# Aero_Board_2022.net
KiCad netlist of a schematic drawn in EAGLE
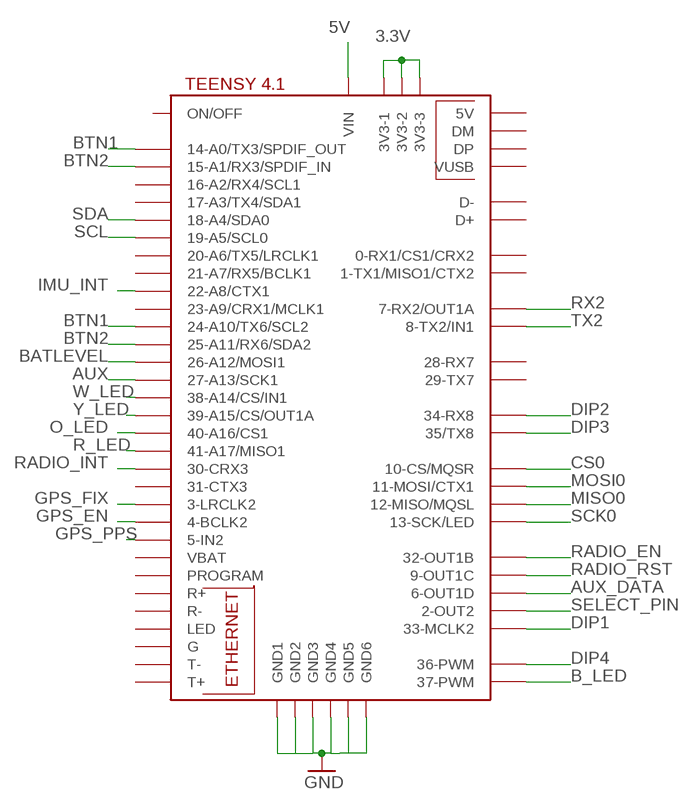
[diagram p0: schematic, sheet 1]
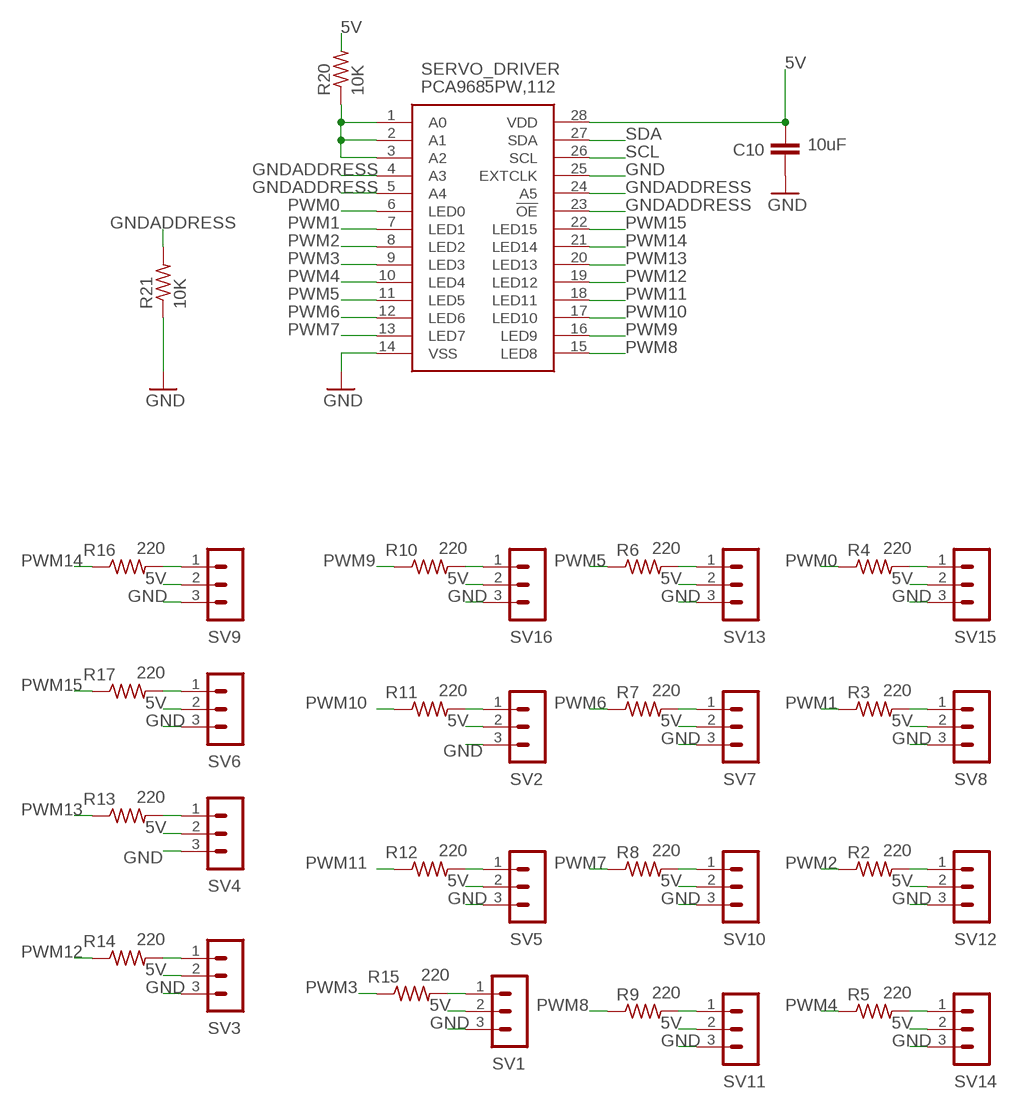
[diagram p1: schematic, sheet 2]
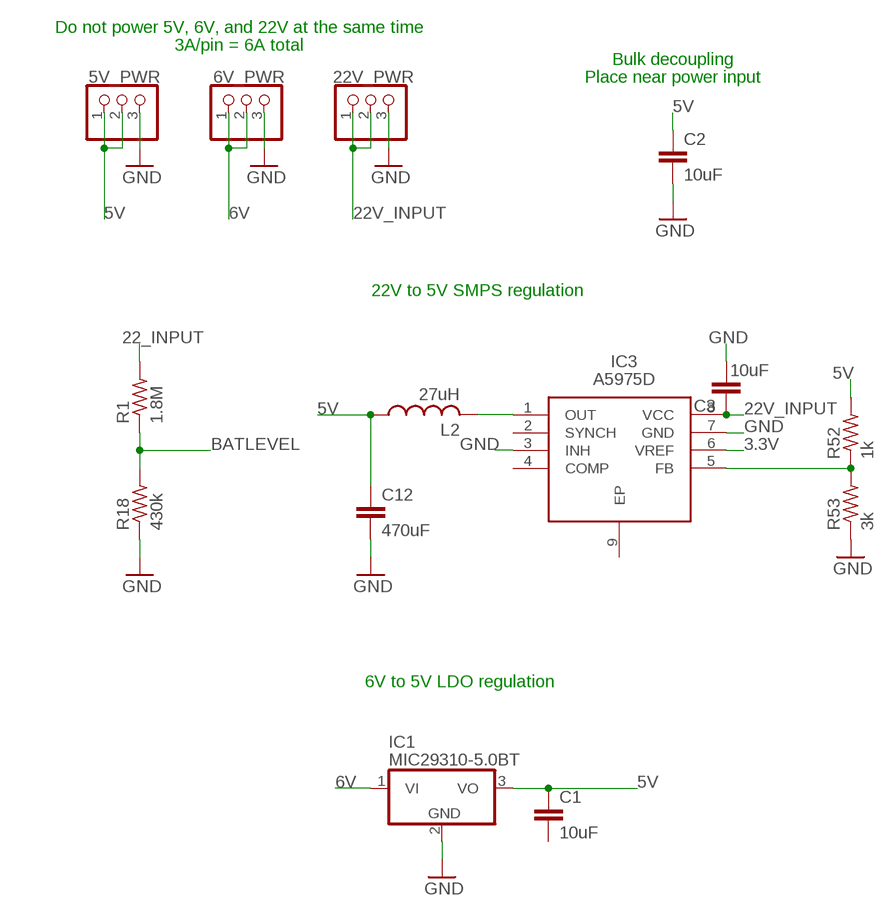
[diagram p2: schematic, sheet 3]
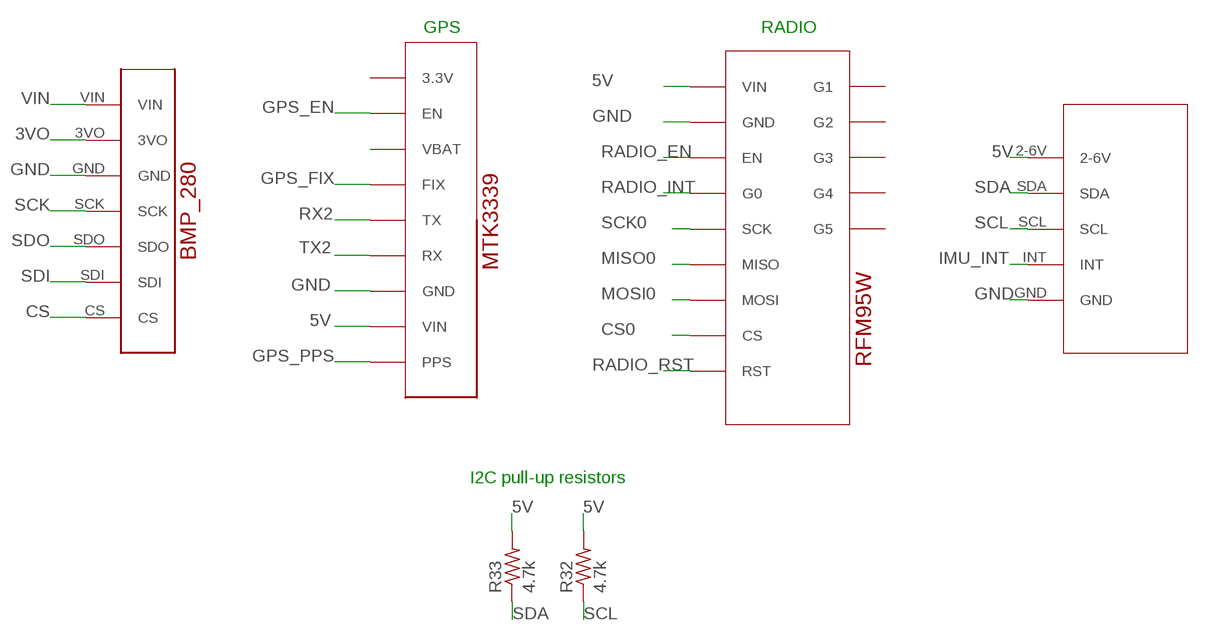
[diagram p3: schematic, sheet 4]
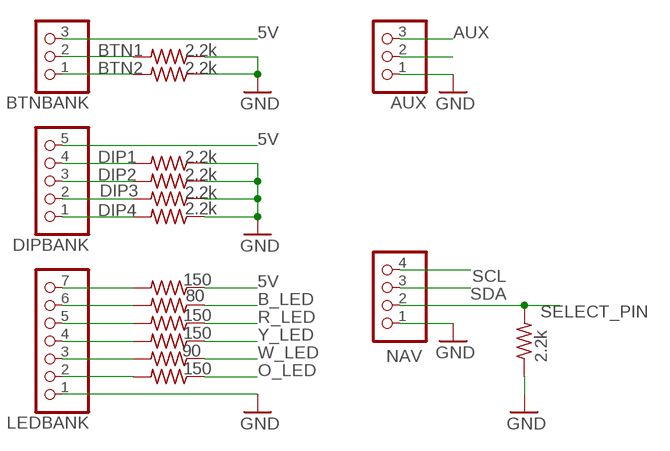
[diagram p4: schematic, sheet 5]
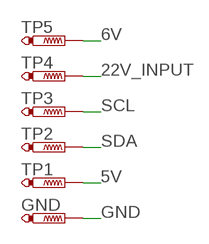
[diagram p5: schematic, sheet 6]

(export (version "E")
  (design (tool "Eeschema 10.0.6"))
  (components
    (comp (ref "TEENSY4.1")
      (value "TEENSY41")
      (footprint "eagle-import:TEENSY41")
      (libsource (lib "eagle-import") (part "TEENSY41"))
    )
    (comp (ref "GND")
      (value "PTR1B1,27")
      (footprint "eagle-import:B1,27")
      (libsource (lib "eagle-import") (part "PTR1B1,27"))
    )
    (comp (ref "TP1")
      (value "PTR1B1,27")
      (footprint "eagle-import:B1,27")
      (libsource (lib "eagle-import") (part "PTR1B1,27"))
    )
    (comp (ref "TP2")
      (value "PTR1B1,27")
      (footprint "eagle-import:B1,27")
      (libsource (lib "eagle-import") (part "PTR1B1,27"))
    )
    (comp (ref "TP3")
      (value "PTR1B1,27")
      (footprint "eagle-import:B1,27")
      (libsource (lib "eagle-import") (part "PTR1B1,27"))
    )
    (comp (ref "TP4")
      (value "PTR1B1,27")
      (footprint "eagle-import:B1,27")
      (libsource (lib "eagle-import") (part "PTR1B1,27"))
    )
    (comp (ref "TP5")
      (value "PTR1B1,27")
      (footprint "eagle-import:B1,27")
      (libsource (lib "eagle-import") (part "PTR1B1,27"))
    )
    (comp (ref "GPSMTK3339")
      (value "ADAFRUIT_MTK3339_GPS")
      (footprint "eagle-import:ADAFRUIT_MTK3339_GPS")
      (libsource (lib "eagle-import") (part "ADAFRUIT_MTK3339_GPS"))
    )
    (comp (ref "IMU")
      (value "ICM20948BREAKOUTDEVICE")
      (footprint "eagle-import:ICM20948BREAKOUT")
      (fields (field (name "SPICEPREFIX") "X"))
      (libsource (lib "eagle-import") (part "ICM20948BREAKOUTDEVICE"))
    )
    (comp (ref "R32")
      (value "4.7k")
      (footprint "eagle-import:0204_7")
      (libsource (lib "eagle-import") (part "R-US_0204/7"))
    )
    (comp (ref "R33")
      (value "4.7k")
      (footprint "eagle-import:0204_7")
      (libsource (lib "eagle-import") (part "R-US_0204/7"))
    )
    (comp (ref "RADIO")
      (value "ADAFRUIT_RFM95W_LORA_RADIO")
      (footprint "eagle-import:ADAFRUIT_RFM95W_LORA_RADIO")
      (libsource (lib "eagle-import") (part "ADAFRUIT_RFM95W_LORA_RADIO"))
    )
    (comp (ref "U1")
      (value "ADAFRUIT_BMP280_BAROMETER")
      (footprint "eagle-import:ADAFRUIT_BMP280_BAROMETER")
      (libsource (lib "eagle-import") (part "ADAFRUIT_BMP280_BAROMETER"))
    )
    (comp (ref "5V_PWR")
      (value "PINHD-1X3")
      (footprint "eagle-import:1X03")
      (libsource (lib "eagle-import") (part "PINHD-1X3"))
    )
    (comp (ref "6V_PWR")
      (value "PINHD-1X3")
      (footprint "eagle-import:1X03")
      (libsource (lib "eagle-import") (part "PINHD-1X3"))
    )
    (comp (ref "22V_PWR")
      (value "PINHD-1X3")
      (footprint "eagle-import:1X03")
      (libsource (lib "eagle-import") (part "PINHD-1X3"))
    )
    (comp (ref "C1")
      (value "10uF")
      (footprint "eagle-import:C2.5-3")
      (libsource (lib "eagle-import") (part "C2,5-3"))
    )
    (comp (ref "C2")
      (value "10uF")
      (footprint "eagle-import:C2.5-3")
      (libsource (lib "eagle-import") (part "C2,5-3"))
    )
    (comp (ref "C3")
      (value "10uF")
      (footprint "eagle-import:C2.5-3")
      (libsource (lib "eagle-import") (part "C2,5-3"))
    )
    (comp (ref "C12")
      (value "470uF")
      (footprint "eagle-import:C2.5-3")
      (libsource (lib "eagle-import") (part "C2,5-3"))
    )
    (comp (ref "IC1")
      (value "MIC29310-5.0BT")
      (footprint "eagle-import:TO220V")
      (libsource (lib "eagle-import") (part "78TV6"))
    )
    (comp (ref "IC3")
      (value "A5975D")
      (footprint "eagle-import:SOIC127P600X170-9N")
      (fields (field (name "MOUSER_PART_NUMBER") "511-A5975D"))
      (libsource (lib "eagle-import") (part "A5975D"))
    )
    (comp (ref "L2")
      (value "27uH")
      (footprint "eagle-import:TFI0307")
      (libsource (lib "eagle-import") (part "L-USTFI0307"))
    )
    (comp (ref "R1")
      (value "1.8M")
      (footprint "eagle-import:0204_7")
      (libsource (lib "eagle-import") (part "R-US_0204/7"))
    )
    (comp (ref "R18")
      (value "430k")
      (footprint "eagle-import:0204_7")
      (libsource (lib "eagle-import") (part "R-US_0204/7"))
    )
    (comp (ref "R52")
      (value "1k")
      (footprint "eagle-import:0204_7")
      (libsource (lib "eagle-import") (part "R-US_0204/7"))
    )
    (comp (ref "R53")
      (value "3k")
      (footprint "eagle-import:0204_7")
      (libsource (lib "eagle-import") (part "R-US_0204/7"))
    )
    (comp (ref "C10")
      (value "10uF")
      (footprint "eagle-import:C2.5-3")
      (libsource (lib "eagle-import") (part "C2,5-3"))
    )
    (comp (ref "R2")
      (value "220")
      (footprint "eagle-import:0204_7")
      (libsource (lib "eagle-import") (part "R-US_0204/7"))
    )
    (comp (ref "R3")
      (value "220")
      (footprint "eagle-import:0204_7")
      (libsource (lib "eagle-import") (part "R-US_0204/7"))
    )
    (comp (ref "R4")
      (value "220")
      (footprint "eagle-import:0204_7")
      (libsource (lib "eagle-import") (part "R-US_0204/7"))
    )
    (comp (ref "R5")
      (value "220")
      (footprint "eagle-import:0204_7")
      (libsource (lib "eagle-import") (part "R-US_0204/7"))
    )
    (comp (ref "R6")
      (value "220")
      (footprint "eagle-import:0204_7")
      (libsource (lib "eagle-import") (part "R-US_0204/7"))
    )
    (comp (ref "R7")
      (value "220")
      (footprint "eagle-import:0204_7")
      (libsource (lib "eagle-import") (part "R-US_0204/7"))
    )
    (comp (ref "R8")
      (value "220")
      (footprint "eagle-import:0204_7")
      (libsource (lib "eagle-import") (part "R-US_0204/7"))
    )
    (comp (ref "R9")
      (value "220")
      (footprint "eagle-import:0204_7")
      (libsource (lib "eagle-import") (part "R-US_0204/7"))
    )
    (comp (ref "R10")
      (value "220")
      (footprint "eagle-import:0204_7")
      (libsource (lib "eagle-import") (part "R-US_0204/7"))
    )
    (comp (ref "R11")
      (value "220")
      (footprint "eagle-import:0204_7")
      (libsource (lib "eagle-import") (part "R-US_0204/7"))
    )
    (comp (ref "R12")
      (value "220")
      (footprint "eagle-import:0204_7")
      (libsource (lib "eagle-import") (part "R-US_0204/7"))
    )
    (comp (ref "R13")
      (value "220")
      (footprint "eagle-import:0204_7")
      (libsource (lib "eagle-import") (part "R-US_0204/7"))
    )
    (comp (ref "R14")
      (value "220")
      (footprint "eagle-import:0204_7")
      (libsource (lib "eagle-import") (part "R-US_0204/7"))
    )
    (comp (ref "R15")
      (value "220")
      (footprint "eagle-import:0204_7")
      (libsource (lib "eagle-import") (part "R-US_0204/7"))
    )
    (comp (ref "R16")
      (value "220")
      (footprint "eagle-import:0204_7")
      (libsource (lib "eagle-import") (part "R-US_0204/7"))
    )
    (comp (ref "R17")
      (value "220")
      (footprint "eagle-import:0204_7")
      (libsource (lib "eagle-import") (part "R-US_0204/7"))
    )
    (comp (ref "R20")
      (value "10K")
      (footprint "eagle-import:0204_7")
      (libsource (lib "eagle-import") (part "R-US_0204/7"))
    )
    (comp (ref "R21")
      (value "10K")
      (footprint "eagle-import:0204_7")
      (libsource (lib "eagle-import") (part "R-US_0204/7"))
    )
    (comp (ref "SERVO_DRIVER")
      (value "PCA9685PW,112")
      (footprint "eagle-import:SOP65P640X110-28N")
      (fields (field (name "MOUSER_PART_NUMBER") "771-PCA9685PW,112"))
      (libsource (lib "eagle-import") (part "PCA9685PW,112"))
    )
    (comp (ref "SV1")
      (value "MA03-1")
      (footprint "eagle-import:MA03-1")
      (libsource (lib "eagle-import") (part "MA03-1"))
    )
    (comp (ref "SV2")
      (value "MA03-1")
      (footprint "eagle-import:MA03-1")
      (libsource (lib "eagle-import") (part "MA03-1"))
    )
    (comp (ref "SV3")
      (value "MA03-1")
      (footprint "eagle-import:MA03-1")
      (libsource (lib "eagle-import") (part "MA03-1"))
    )
    (comp (ref "SV4")
      (value "MA03-1")
      (footprint "eagle-import:MA03-1")
      (libsource (lib "eagle-import") (part "MA03-1"))
    )
    (comp (ref "SV5")
      (value "MA03-1")
      (footprint "eagle-import:MA03-1")
      (libsource (lib "eagle-import") (part "MA03-1"))
    )
    (comp (ref "SV6")
      (value "MA03-1")
      (footprint "eagle-import:MA03-1")
      (libsource (lib "eagle-import") (part "MA03-1"))
    )
    (comp (ref "SV7")
      (value "MA03-1")
      (footprint "eagle-import:MA03-1")
      (libsource (lib "eagle-import") (part "MA03-1"))
    )
    (comp (ref "SV8")
      (value "MA03-1")
      (footprint "eagle-import:MA03-1")
      (libsource (lib "eagle-import") (part "MA03-1"))
    )
    (comp (ref "SV9")
      (value "MA03-1")
      (footprint "eagle-import:MA03-1")
      (libsource (lib "eagle-import") (part "MA03-1"))
    )
    (comp (ref "SV10")
      (value "MA03-1")
      (footprint "eagle-import:MA03-1")
      (libsource (lib "eagle-import") (part "MA03-1"))
    )
    (comp (ref "SV11")
      (value "MA03-1")
      (footprint "eagle-import:MA03-1")
      (libsource (lib "eagle-import") (part "MA03-1"))
    )
    (comp (ref "SV12")
      (value "MA03-1")
      (footprint "eagle-import:MA03-1")
      (libsource (lib "eagle-import") (part "MA03-1"))
    )
    (comp (ref "SV13")
      (value "MA03-1")
      (footprint "eagle-import:MA03-1")
      (libsource (lib "eagle-import") (part "MA03-1"))
    )
    (comp (ref "SV14")
      (value "MA03-1")
      (footprint "eagle-import:MA03-1")
      (libsource (lib "eagle-import") (part "MA03-1"))
    )
    (comp (ref "SV15")
      (value "MA03-1")
      (footprint "eagle-import:MA03-1")
      (libsource (lib "eagle-import") (part "MA03-1"))
    )
    (comp (ref "SV16")
      (value "MA03-1")
      (footprint "eagle-import:MA03-1")
      (libsource (lib "eagle-import") (part "MA03-1"))
    )
    (comp (ref "AUX")
      (value "PINHD-1X3")
      (footprint "eagle-import:1X03")
      (libsource (lib "eagle-import") (part "PINHD-1X3"))
    )
    (comp (ref "BLUE")
      (value "80")
      (footprint "eagle-import:0204_7")
      (libsource (lib "eagle-import") (part "R-US_0204/7"))
    )
    (comp (ref "BTNBANK")
      (value "PINHD-1X3")
      (footprint "eagle-import:1X03")
      (libsource (lib "eagle-import") (part "PINHD-1X3"))
    )
    (comp (ref "DIPBANK")
      (value "PINHD-1X5")
      (footprint "eagle-import:1X05")
      (libsource (lib "eagle-import") (part "PINHD-1X5"))
    )
    (comp (ref "GREEN")
      (value "150")
      (footprint "eagle-import:0204_7")
      (libsource (lib "eagle-import") (part "R-US_0204/7"))
    )
    (comp (ref "LEDBANK")
      (value "PINHD-1X7")
      (footprint "eagle-import:1X07")
      (libsource (lib "eagle-import") (part "PINHD-1X7"))
    )
    (comp (ref "NAV")
      (value "PINHD-1X4")
      (footprint "eagle-import:1X04")
      (libsource (lib "eagle-import") (part "PINHD-1X4"))
    )
    (comp (ref "ORANGE")
      (value "150")
      (footprint "eagle-import:0204_7")
      (libsource (lib "eagle-import") (part "R-US_0204/7"))
    )
    (comp (ref "R19")
      (value "2.2k")
      (footprint "eagle-import:0204_7")
      (libsource (lib "eagle-import") (part "R-US_0204/7"))
    )
    (comp (ref "R22")
      (value "2.2k")
      (footprint "eagle-import:0204_7")
      (libsource (lib "eagle-import") (part "R-US_0204/7"))
    )
    (comp (ref "R23")
      (value "2.2k")
      (footprint "eagle-import:0204_7")
      (libsource (lib "eagle-import") (part "R-US_0204/7"))
    )
    (comp (ref "R34")
      (value "2.2k")
      (footprint "eagle-import:0204_7")
      (libsource (lib "eagle-import") (part "R-US_0204/7"))
    )
    (comp (ref "R35")
      (value "2.2k")
      (footprint "eagle-import:0204_7")
      (libsource (lib "eagle-import") (part "R-US_0204/7"))
    )
    (comp (ref "R36")
      (value "2.2k")
      (footprint "eagle-import:0204_7")
      (libsource (lib "eagle-import") (part "R-US_0204/7"))
    )
    (comp (ref "R37")
      (value "2.2k")
      (footprint "eagle-import:0204_7")
      (libsource (lib "eagle-import") (part "R-US_0204/7"))
    )
    (comp (ref "RED")
      (value "150")
      (footprint "eagle-import:0204_7")
      (libsource (lib "eagle-import") (part "R-US_0204/7"))
    )
    (comp (ref "WHITE")
      (value "90")
      (footprint "eagle-import:0204_7")
      (libsource (lib "eagle-import") (part "R-US_0204/7"))
    )
    (comp (ref "YELLOW")
      (value "150")
      (footprint "eagle-import:0204_7")
      (libsource (lib "eagle-import") (part "R-US_0204/7"))
    )
  )
  (nets
    (net (code "1") (name "3.3V") (class "Default")
      (node (ref "IC3") (pin "6") (pinfunction "VREF_6") (pintype "bidirectional"))
      (node (ref "TEENSY4.1") (pin "3V3-1") (pinfunction "3V3-1_3V3-1") (pintype "bidirectional"))
      (node (ref "TEENSY4.1") (pin "3V3-2") (pinfunction "3V3-2_3V3-2") (pintype "bidirectional"))
      (node (ref "TEENSY4.1") (pin "3V3-3") (pinfunction "3V3-3_3V3-3") (pintype "bidirectional"))
    )
    (net (code "2") (name "3VO") (class "Default")
      (node (ref "U1") (pin "3VO") (pinfunction "3VO_3VO") (pintype "bidirectional"))
    )
    (net (code "3") (name "5V") (class "Default")
      (node (ref "5V_PWR") (pin "1") (pinfunction "1_1") (pintype "passive"))
      (node (ref "5V_PWR") (pin "2") (pinfunction "2_2") (pintype "passive"))
      (node (ref "BTNBANK") (pin "3") (pinfunction "3_3") (pintype "passive"))
      (node (ref "C1") (pin "1") (pinfunction "1_1") (pintype "passive"))
      (node (ref "C10") (pin "1") (pinfunction "1_1") (pintype "passive"))
      (node (ref "C12") (pin "1") (pinfunction "1_1") (pintype "passive"))
      (node (ref "C2") (pin "1") (pinfunction "1_1") (pintype "passive"))
      (node (ref "DIPBANK") (pin "5") (pinfunction "5_5") (pintype "passive"))
      (node (ref "GPSMTK3339") (pin "VIN") (pinfunction "VIN_VIN") (pintype "bidirectional"))
      (node (ref "GREEN") (pin "1") (pinfunction "1_1") (pintype "passive"))
      (node (ref "IC1") (pin "3") (pinfunction "VO_3") (pintype "passive"))
      (node (ref "IMU") (pin "2-6V") (pinfunction "2-6V_2-6V") (pintype "bidirectional"))
      (node (ref "L2") (pin "1") (pinfunction "1_1") (pintype "passive"))
      (node (ref "R20") (pin "2") (pinfunction "2_2") (pintype "passive"))
      (node (ref "R32") (pin "2") (pinfunction "2_2") (pintype "passive"))
      (node (ref "R33") (pin "2") (pinfunction "2_2") (pintype "passive"))
      (node (ref "R52") (pin "2") (pinfunction "2_2") (pintype "passive"))
      (node (ref "RADIO") (pin "1") (pinfunction "VIN_1") (pintype "bidirectional"))
      (node (ref "SERVO_DRIVER") (pin "28") (pinfunction "VDD_28") (pintype "bidirectional"))
      (node (ref "SV1") (pin "2") (pinfunction "2_2") (pintype "passive"))
      (node (ref "SV10") (pin "2") (pinfunction "2_2") (pintype "passive"))
      (node (ref "SV11") (pin "2") (pinfunction "2_2") (pintype "passive"))
      (node (ref "SV12") (pin "2") (pinfunction "2_2") (pintype "passive"))
      (node (ref "SV13") (pin "2") (pinfunction "2_2") (pintype "passive"))
      (node (ref "SV14") (pin "2") (pinfunction "2_2") (pintype "passive"))
      (node (ref "SV15") (pin "2") (pinfunction "2_2") (pintype "passive"))
      (node (ref "SV16") (pin "2") (pinfunction "2_2") (pintype "passive"))
      (node (ref "SV2") (pin "2") (pinfunction "2_2") (pintype "passive"))
      (node (ref "SV3") (pin "2") (pinfunction "2_2") (pintype "passive"))
      (node (ref "SV4") (pin "2") (pinfunction "2_2") (pintype "passive"))
      (node (ref "SV5") (pin "2") (pinfunction "2_2") (pintype "passive"))
      (node (ref "SV6") (pin "2") (pinfunction "2_2") (pintype "passive"))
      (node (ref "SV7") (pin "2") (pinfunction "2_2") (pintype "passive"))
      (node (ref "SV8") (pin "2") (pinfunction "2_2") (pintype "passive"))
      (node (ref "SV9") (pin "2") (pinfunction "2_2") (pintype "passive"))
      (node (ref "TEENSY4.1") (pin "VIN") (pinfunction "VIN_VIN") (pintype "bidirectional"))
      (node (ref "TP1") (pin "TP") (pinfunction "TP_TP") (pintype "input"))
    )
    (net (code "4") (name "6V") (class "Default")
      (node (ref "6V_PWR") (pin "1") (pinfunction "1_1") (pintype "passive"))
      (node (ref "6V_PWR") (pin "2") (pinfunction "2_2") (pintype "passive"))
      (node (ref "IC1") (pin "1") (pinfunction "VI_1") (pintype "input"))
      (node (ref "TP5") (pin "TP") (pinfunction "TP_TP") (pintype "input"))
    )
    (net (code "5") (name "22V_INPUT") (class "Default")
      (node (ref "22V_PWR") (pin "1") (pinfunction "1_1") (pintype "passive"))
      (node (ref "22V_PWR") (pin "2") (pinfunction "2_2") (pintype "passive"))
      (node (ref "C3") (pin "1") (pinfunction "1_1") (pintype "passive"))
      (node (ref "IC3") (pin "8") (pinfunction "VCC_8") (pintype "bidirectional"))
      (node (ref "TP4") (pin "TP") (pinfunction "TP_TP") (pintype "input"))
    )
    (net (code "6") (name "22_INPUT") (class "Default")
      (node (ref "R1") (pin "2") (pinfunction "2_2") (pintype "passive"))
    )
    (net (code "7") (name "AUX") (class "Default")
      (node (ref "AUX") (pin "3") (pinfunction "3_3") (pintype "passive"))
      (node (ref "TEENSY4.1") (pin "27-A13/SCK1") (pinfunction "27-A13/SCK1_27-A13/SCK1") (pintype "bidirectional"))
    )
    (net (code "8") (name "AUX_DATA") (class "Default")
      (node (ref "TEENSY4.1") (pin "6-OUT1D") (pinfunction "6-OUT1D_6-OUT1D") (pintype "bidirectional"))
    )
    (net (code "9") (name "BATLEVEL") (class "Default")
      (node (ref "R1") (pin "1") (pinfunction "1_1") (pintype "passive"))
      (node (ref "R18") (pin "2") (pinfunction "2_2") (pintype "passive"))
      (node (ref "TEENSY4.1") (pin "26-A12/MOSI1") (pinfunction "26-A12/MOSI1_26-A12/MOSI1") (pintype "bidirectional"))
    )
    (net (code "10") (name "BTN1") (class "Default")
      (node (ref "BTNBANK") (pin "2") (pinfunction "2_2") (pintype "passive"))
      (node (ref "R19") (pin "2") (pinfunction "2_2") (pintype "passive"))
      (node (ref "TEENSY4.1") (pin "14-A0/TX3/SPDIF_OUT") (pinfunction "14-A0/TX3/SPDIF_OUT_14-A0/TX3/SPDIF_OUT") (pintype "bidirectional"))
      (node (ref "TEENSY4.1") (pin "24-A10/TX6/SCL2") (pinfunction "24-A10/TX6/SCL2_24-A10/TX6/SCL2") (pintype "bidirectional"))
    )
    (net (code "11") (name "BTN2") (class "Default")
      (node (ref "BTNBANK") (pin "1") (pinfunction "1_1") (pintype "passive"))
      (node (ref "R22") (pin "2") (pinfunction "2_2") (pintype "passive"))
      (node (ref "TEENSY4.1") (pin "15-A1/RX3/SPDIF_IN") (pinfunction "15-A1/RX3/SPDIF_IN_15-A1/RX3/SPDIF_IN") (pintype "bidirectional"))
      (node (ref "TEENSY4.1") (pin "25-A11/RX6/SDA2") (pinfunction "25-A11/RX6/SDA2_25-A11/RX6/SDA2") (pintype "bidirectional"))
    )
    (net (code "12") (name "B_LED") (class "Default")
      (node (ref "BLUE") (pin "1") (pinfunction "1_1") (pintype "passive"))
      (node (ref "TEENSY4.1") (pin "37-PWM") (pinfunction "37-PWM_37-PWM") (pintype "bidirectional"))
    )
    (net (code "13") (name "CS") (class "Default")
      (node (ref "U1") (pin "CS") (pinfunction "CS_CS") (pintype "bidirectional"))
    )
    (net (code "14") (name "CS0") (class "Default")
      (node (ref "RADIO") (pin "8") (pinfunction "CS_8") (pintype "bidirectional"))
      (node (ref "TEENSY4.1") (pin "10-CS\\MQSR") (pinfunction "10-CS/MQSR_10-CS\\MQSR") (pintype "bidirectional"))
    )
    (net (code "15") (name "DIP1") (class "Default")
      (node (ref "DIPBANK") (pin "4") (pinfunction "4_4") (pintype "passive"))
      (node (ref "R37") (pin "2") (pinfunction "2_2") (pintype "passive"))
      (node (ref "TEENSY4.1") (pin "33-MCLK2") (pinfunction "33-MCLK2_33-MCLK2") (pintype "bidirectional"))
    )
    (net (code "16") (name "DIP2") (class "Default")
      (node (ref "DIPBANK") (pin "3") (pinfunction "3_3") (pintype "passive"))
      (node (ref "R36") (pin "2") (pinfunction "2_2") (pintype "passive"))
      (node (ref "TEENSY4.1") (pin "34-RX8") (pinfunction "34-RX8_34-RX8") (pintype "bidirectional"))
    )
    (net (code "17") (name "DIP3") (class "Default")
      (node (ref "DIPBANK") (pin "2") (pinfunction "2_2") (pintype "passive"))
      (node (ref "R34") (pin "2") (pinfunction "2_2") (pintype "passive"))
      (node (ref "TEENSY4.1") (pin "35-TX8") (pinfunction "35/TX8_35-TX8") (pintype "bidirectional"))
    )
    (net (code "18") (name "DIP4") (class "Default")
      (node (ref "DIPBANK") (pin "1") (pinfunction "1_1") (pintype "passive"))
      (node (ref "R35") (pin "2") (pinfunction "2_2") (pintype "passive"))
      (node (ref "TEENSY4.1") (pin "36-PWM") (pinfunction "36-PWM_36-PWM") (pintype "bidirectional"))
    )
    (net (code "19") (name "GND") (class "Default")
      (node (ref "22V_PWR") (pin "3") (pinfunction "3_3") (pintype "passive"))
      (node (ref "5V_PWR") (pin "3") (pinfunction "3_3") (pintype "passive"))
      (node (ref "6V_PWR") (pin "3") (pinfunction "3_3") (pintype "passive"))
      (node (ref "AUX") (pin "1") (pinfunction "1_1") (pintype "passive"))
      (node (ref "C10") (pin "2") (pinfunction "2_2") (pintype "passive"))
      (node (ref "C12") (pin "2") (pinfunction "2_2") (pintype "passive"))
      (node (ref "C2") (pin "2") (pinfunction "2_2") (pintype "passive"))
      (node (ref "C3") (pin "2") (pinfunction "2_2") (pintype "passive"))
      (node (ref "GND") (pin "TP") (pinfunction "TP_TP") (pintype "input"))
      (node (ref "GPSMTK3339") (pin "GND") (pinfunction "GND_GND") (pintype "bidirectional"))
      (node (ref "IC1") (pin "2") (pinfunction "GND_2") (pintype "passive"))
      (node (ref "IC3") (pin "3") (pinfunction "INH_3") (pintype "bidirectional"))
      (node (ref "IC3") (pin "7") (pinfunction "GND_7") (pintype "bidirectional"))
      (node (ref "IMU") (pin "GND") (pinfunction "GND_GND") (pintype "bidirectional"))
      (node (ref "LEDBANK") (pin "1") (pinfunction "1_1") (pintype "passive"))
      (node (ref "NAV") (pin "1") (pinfunction "1_1") (pintype "passive"))
      (node (ref "R18") (pin "1") (pinfunction "1_1") (pintype "passive"))
      (node (ref "R19") (pin "1") (pinfunction "1_1") (pintype "passive"))
      (node (ref "R21") (pin "1") (pinfunction "1_1") (pintype "passive"))
      (node (ref "R22") (pin "1") (pinfunction "1_1") (pintype "passive"))
      (node (ref "R23") (pin "1") (pinfunction "1_1") (pintype "passive"))
      (node (ref "R34") (pin "1") (pinfunction "1_1") (pintype "passive"))
      (node (ref "R35") (pin "1") (pinfunction "1_1") (pintype "passive"))
      (node (ref "R36") (pin "1") (pinfunction "1_1") (pintype "passive"))
      (node (ref "R37") (pin "1") (pinfunction "1_1") (pintype "passive"))
      (node (ref "R53") (pin "1") (pinfunction "1_1") (pintype "passive"))
      (node (ref "RADIO") (pin "2") (pinfunction "GND_2") (pintype "bidirectional"))
      (node (ref "SERVO_DRIVER") (pin "14") (pinfunction "VSS_14") (pintype "bidirectional"))
      (node (ref "SERVO_DRIVER") (pin "25") (pinfunction "EXTCLK_25") (pintype "bidirectional"))
      (node (ref "SV1") (pin "3") (pinfunction "3_3") (pintype "passive"))
      (node (ref "SV10") (pin "3") (pinfunction "3_3") (pintype "passive"))
      (node (ref "SV11") (pin "3") (pinfunction "3_3") (pintype "passive"))
      (node (ref "SV12") (pin "3") (pinfunction "3_3") (pintype "passive"))
      (node (ref "SV13") (pin "3") (pinfunction "3_3") (pintype "passive"))
      (node (ref "SV14") (pin "3") (pinfunction "3_3") (pintype "passive"))
      (node (ref "SV15") (pin "3") (pinfunction "3_3") (pintype "passive"))
      (node (ref "SV16") (pin "3") (pinfunction "3_3") (pintype "passive"))
      (node (ref "SV2") (pin "3") (pinfunction "3_3") (pintype "passive"))
      (node (ref "SV3") (pin "3") (pinfunction "3_3") (pintype "passive"))
      (node (ref "SV4") (pin "3") (pinfunction "3_3") (pintype "passive"))
      (node (ref "SV5") (pin "3") (pinfunction "3_3") (pintype "passive"))
      (node (ref "SV6") (pin "3") (pinfunction "3_3") (pintype "passive"))
      (node (ref "SV7") (pin "3") (pinfunction "3_3") (pintype "passive"))
      (node (ref "SV8") (pin "3") (pinfunction "3_3") (pintype "passive"))
      (node (ref "SV9") (pin "3") (pinfunction "3_3") (pintype "passive"))
      (node (ref "TEENSY4.1") (pin "GND1") (pinfunction "GND1_GND1") (pintype "bidirectional"))
      (node (ref "TEENSY4.1") (pin "GND2") (pinfunction "GND2_GND2") (pintype "bidirectional"))
      (node (ref "TEENSY4.1") (pin "GND3") (pinfunction "GND3_GND3") (pintype "bidirectional"))
      (node (ref "TEENSY4.1") (pin "GND4") (pinfunction "GND4_GND4") (pintype "bidirectional"))
      (node (ref "TEENSY4.1") (pin "GND5") (pinfunction "GND5_GND5") (pintype "bidirectional"))
      (node (ref "TEENSY4.1") (pin "GND6") (pinfunction "GND6_GND6") (pintype "bidirectional"))
      (node (ref "U1") (pin "GND") (pinfunction "GND_GND") (pintype "power_in"))
    )
    (net (code "20") (name "GNDADDRESS") (class "Default")
      (node (ref "R21") (pin "2") (pinfunction "2_2") (pintype "passive"))
      (node (ref "SERVO_DRIVER") (pin "23") (pinfunction "~{OE}_23") (pintype "bidirectional"))
      (node (ref "SERVO_DRIVER") (pin "24") (pinfunction "A5_24") (pintype "bidirectional"))
      (node (ref "SERVO_DRIVER") (pin "4") (pinfunction "A3_4") (pintype "bidirectional"))
      (node (ref "SERVO_DRIVER") (pin "5") (pinfunction "A4_5") (pintype "bidirectional"))
    )
    (net (code "21") (name "GPS_EN") (class "Default")
      (node (ref "GPSMTK3339") (pin "EN") (pinfunction "EN_EN") (pintype "bidirectional"))
      (node (ref "TEENSY4.1") (pin "4-BCLK2") (pinfunction "4-BCLK2_4-BCLK2") (pintype "bidirectional"))
    )
    (net (code "22") (name "GPS_FIX") (class "Default")
      (node (ref "GPSMTK3339") (pin "FIX") (pinfunction "FIX_FIX") (pintype "bidirectional"))
      (node (ref "TEENSY4.1") (pin "3-LRCLK2") (pinfunction "3-LRCLK2_3-LRCLK2") (pintype "bidirectional"))
    )
    (net (code "23") (name "GPS_PPS") (class "Default")
      (node (ref "GPSMTK3339") (pin "PPS") (pinfunction "PPS_PPS") (pintype "bidirectional"))
      (node (ref "TEENSY4.1") (pin "5-IN2") (pinfunction "5-IN2_5-IN2") (pintype "bidirectional"))
    )
    (net (code "24") (name "IMU_INT") (class "Default")
      (node (ref "IMU") (pin "INT") (pinfunction "INT_INT") (pintype "bidirectional"))
      (node (ref "TEENSY4.1") (pin "22-A8/CTX1") (pinfunction "22-A8/CTX1_22-A8/CTX1") (pintype "bidirectional"))
    )
    (net (code "25") (name "MISO0") (class "Default")
      (node (ref "RADIO") (pin "6") (pinfunction "MISO_6") (pintype "bidirectional"))
      (node (ref "TEENSY4.1") (pin "12-MISO/MQSL") (pinfunction "12-MISO/MQSL_12-MISO/MQSL") (pintype "bidirectional"))
    )
    (net (code "26") (name "MOSI0") (class "Default")
      (node (ref "RADIO") (pin "7") (pinfunction "MOSI_7") (pintype "bidirectional"))
      (node (ref "TEENSY4.1") (pin "11-MOSI/CTX1") (pinfunction "11-MOSI/CTX1_11-MOSI/CTX1") (pintype "bidirectional"))
    )
    (net (code "27") (name "Net-(BLUE-Pad2)") (class "Default")
      (node (ref "BLUE") (pin "2") (pinfunction "2_2") (pintype "passive"))
      (node (ref "LEDBANK") (pin "6") (pinfunction "6_6") (pintype "passive"))
    )
    (net (code "28") (name "Net-(GREEN-Pad2)") (class "Default")
      (node (ref "GREEN") (pin "2") (pinfunction "2_2") (pintype "passive"))
      (node (ref "LEDBANK") (pin "7") (pinfunction "7_7") (pintype "passive"))
    )
    (net (code "29") (name "Net-(IC3-FB)") (class "Default")
      (node (ref "IC3") (pin "5") (pinfunction "FB_5") (pintype "bidirectional"))
      (node (ref "R52") (pin "1") (pinfunction "1_1") (pintype "passive"))
      (node (ref "R53") (pin "2") (pinfunction "2_2") (pintype "passive"))
    )
    (net (code "30") (name "Net-(IC3-OUT)") (class "Default")
      (node (ref "IC3") (pin "1") (pinfunction "OUT_1") (pintype "bidirectional"))
      (node (ref "L2") (pin "2") (pinfunction "2_2") (pintype "passive"))
    )
    (net (code "31") (name "Net-(LEDBANK-Pad2)") (class "Default")
      (node (ref "LEDBANK") (pin "2") (pinfunction "2_2") (pintype "passive"))
      (node (ref "ORANGE") (pin "2") (pinfunction "2_2") (pintype "passive"))
    )
    (net (code "32") (name "Net-(LEDBANK-Pad3)") (class "Default")
      (node (ref "LEDBANK") (pin "3") (pinfunction "3_3") (pintype "passive"))
      (node (ref "WHITE") (pin "2") (pinfunction "2_2") (pintype "passive"))
    )
    (net (code "33") (name "Net-(LEDBANK-Pad4)") (class "Default")
      (node (ref "LEDBANK") (pin "4") (pinfunction "4_4") (pintype "passive"))
      (node (ref "YELLOW") (pin "2") (pinfunction "2_2") (pintype "passive"))
    )
    (net (code "34") (name "Net-(LEDBANK-Pad5)") (class "Default")
      (node (ref "LEDBANK") (pin "5") (pinfunction "5_5") (pintype "passive"))
      (node (ref "RED") (pin "2") (pinfunction "2_2") (pintype "passive"))
    )
    (net (code "35") (name "Net-(R2-Pad2)") (class "Default")
      (node (ref "R2") (pin "2") (pinfunction "2_2") (pintype "passive"))
      (node (ref "SV12") (pin "1") (pinfunction "1_1") (pintype "passive"))
    )
    (net (code "36") (name "Net-(R3-Pad2)") (class "Default")
      (node (ref "R3") (pin "2") (pinfunction "2_2") (pintype "passive"))
      (node (ref "SV8") (pin "1") (pinfunction "1_1") (pintype "passive"))
    )
    (net (code "37") (name "Net-(R4-Pad2)") (class "Default")
      (node (ref "R4") (pin "2") (pinfunction "2_2") (pintype "passive"))
      (node (ref "SV15") (pin "1") (pinfunction "1_1") (pintype "passive"))
    )
    (net (code "38") (name "Net-(R5-Pad2)") (class "Default")
      (node (ref "R5") (pin "2") (pinfunction "2_2") (pintype "passive"))
      (node (ref "SV14") (pin "1") (pinfunction "1_1") (pintype "passive"))
    )
    (net (code "39") (name "Net-(R6-Pad2)") (class "Default")
      (node (ref "R6") (pin "2") (pinfunction "2_2") (pintype "passive"))
      (node (ref "SV13") (pin "1") (pinfunction "1_1") (pintype "passive"))
    )
    (net (code "40") (name "Net-(R7-Pad2)") (class "Default")
      (node (ref "R7") (pin "2") (pinfunction "2_2") (pintype "passive"))
      (node (ref "SV7") (pin "1") (pinfunction "1_1") (pintype "passive"))
    )
    (net (code "41") (name "Net-(R8-Pad2)") (class "Default")
      (node (ref "R8") (pin "2") (pinfunction "2_2") (pintype "passive"))
      (node (ref "SV10") (pin "1") (pinfunction "1_1") (pintype "passive"))
    )
    (net (code "42") (name "Net-(R9-Pad2)") (class "Default")
      (node (ref "R9") (pin "2") (pinfunction "2_2") (pintype "passive"))
      (node (ref "SV11") (pin "1") (pinfunction "1_1") (pintype "passive"))
    )
    (net (code "43") (name "Net-(R10-Pad2)") (class "Default")
      (node (ref "R10") (pin "2") (pinfunction "2_2") (pintype "passive"))
      (node (ref "SV16") (pin "1") (pinfunction "1_1") (pintype "passive"))
    )
    (net (code "44") (name "Net-(R11-Pad2)") (class "Default")
      (node (ref "R11") (pin "2") (pinfunction "2_2") (pintype "passive"))
      (node (ref "SV2") (pin "1") (pinfunction "1_1") (pintype "passive"))
    )
    (net (code "45") (name "Net-(R12-Pad2)") (class "Default")
      (node (ref "R12") (pin "2") (pinfunction "2_2") (pintype "passive"))
      (node (ref "SV5") (pin "1") (pinfunction "1_1") (pintype "passive"))
    )
    (net (code "46") (name "Net-(R13-Pad2)") (class "Default")
      (node (ref "R13") (pin "2") (pinfunction "2_2") (pintype "passive"))
      (node (ref "SV4") (pin "1") (pinfunction "1_1") (pintype "passive"))
    )
    (net (code "47") (name "Net-(R14-Pad2)") (class "Default")
      (node (ref "R14") (pin "2") (pinfunction "2_2") (pintype "passive"))
      (node (ref "SV3") (pin "1") (pinfunction "1_1") (pintype "passive"))
    )
    (net (code "48") (name "Net-(R15-Pad2)") (class "Default")
      (node (ref "R15") (pin "2") (pinfunction "2_2") (pintype "passive"))
      (node (ref "SV1") (pin "1") (pinfunction "1_1") (pintype "passive"))
    )
    (net (code "49") (name "Net-(R16-Pad2)") (class "Default")
      (node (ref "R16") (pin "2") (pinfunction "2_2") (pintype "passive"))
      (node (ref "SV9") (pin "1") (pinfunction "1_1") (pintype "passive"))
    )
    (net (code "50") (name "Net-(R17-Pad2)") (class "Default")
      (node (ref "R17") (pin "2") (pinfunction "2_2") (pintype "passive"))
      (node (ref "SV6") (pin "1") (pinfunction "1_1") (pintype "passive"))
    )
    (net (code "51") (name "Net-(SERVO_DRIVER-A0)") (class "Default")
      (node (ref "R20") (pin "1") (pinfunction "1_1") (pintype "passive"))
      (node (ref "SERVO_DRIVER") (pin "1") (pinfunction "A0_1") (pintype "bidirectional"))
      (node (ref "SERVO_DRIVER") (pin "2") (pinfunction "A1_2") (pintype "bidirectional"))
      (node (ref "SERVO_DRIVER") (pin "3") (pinfunction "A2_3") (pintype "bidirectional"))
    )
    (net (code "52") (name "O_LED") (class "Default")
      (node (ref "ORANGE") (pin "1") (pinfunction "1_1") (pintype "passive"))
      (node (ref "TEENSY4.1") (pin "40-A16/CS1") (pinfunction "40-A16/CS1_40-A16/CS1") (pintype "bidirectional"))
    )
    (net (code "53") (name "PWM0") (class "Default")
      (node (ref "R4") (pin "1") (pinfunction "1_1") (pintype "passive"))
      (node (ref "SERVO_DRIVER") (pin "6") (pinfunction "LED0_6") (pintype "bidirectional"))
    )
    (net (code "54") (name "PWM1") (class "Default")
      (node (ref "R3") (pin "1") (pinfunction "1_1") (pintype "passive"))
      (node (ref "SERVO_DRIVER") (pin "7") (pinfunction "LED1_7") (pintype "bidirectional"))
    )
    (net (code "55") (name "PWM2") (class "Default")
      (node (ref "R2") (pin "1") (pinfunction "1_1") (pintype "passive"))
      (node (ref "SERVO_DRIVER") (pin "8") (pinfunction "LED2_8") (pintype "bidirectional"))
    )
    (net (code "56") (name "PWM3") (class "Default")
      (node (ref "R15") (pin "1") (pinfunction "1_1") (pintype "passive"))
      (node (ref "SERVO_DRIVER") (pin "9") (pinfunction "LED3_9") (pintype "bidirectional"))
    )
    (net (code "57") (name "PWM4") (class "Default")
      (node (ref "R5") (pin "1") (pinfunction "1_1") (pintype "passive"))
      (node (ref "SERVO_DRIVER") (pin "10") (pinfunction "LED4_10") (pintype "bidirectional"))
    )
    (net (code "58") (name "PWM5") (class "Default")
      (node (ref "R6") (pin "1") (pinfunction "1_1") (pintype "passive"))
      (node (ref "SERVO_DRIVER") (pin "11") (pinfunction "LED5_11") (pintype "bidirectional"))
    )
    (net (code "59") (name "PWM6") (class "Default")
      (node (ref "R7") (pin "1") (pinfunction "1_1") (pintype "passive"))
      (node (ref "SERVO_DRIVER") (pin "12") (pinfunction "LED6_12") (pintype "bidirectional"))
    )
    (net (code "60") (name "PWM7") (class "Default")
      (node (ref "R8") (pin "1") (pinfunction "1_1") (pintype "passive"))
      (node (ref "SERVO_DRIVER") (pin "13") (pinfunction "LED7_13") (pintype "bidirectional"))
    )
    (net (code "61") (name "PWM8") (class "Default")
      (node (ref "R9") (pin "1") (pinfunction "1_1") (pintype "passive"))
      (node (ref "SERVO_DRIVER") (pin "15") (pinfunction "LED8_15") (pintype "bidirectional"))
    )
    (net (code "62") (name "PWM9") (class "Default")
      (node (ref "R10") (pin "1") (pinfunction "1_1") (pintype "passive"))
      (node (ref "SERVO_DRIVER") (pin "16") (pinfunction "LED9_16") (pintype "bidirectional"))
    )
    (net (code "63") (name "PWM10") (class "Default")
      (node (ref "R11") (pin "1") (pinfunction "1_1") (pintype "passive"))
      (node (ref "SERVO_DRIVER") (pin "17") (pinfunction "LED10_17") (pintype "bidirectional"))
    )
    (net (code "64") (name "PWM11") (class "Default")
      (node (ref "R12") (pin "1") (pinfunction "1_1") (pintype "passive"))
      (node (ref "SERVO_DRIVER") (pin "18") (pinfunction "LED11_18") (pintype "bidirectional"))
    )
    (net (code "65") (name "PWM12") (class "Default")
      (node (ref "R14") (pin "1") (pinfunction "1_1") (pintype "passive"))
      (node (ref "SERVO_DRIVER") (pin "19") (pinfunction "LED12_19") (pintype "bidirectional"))
    )
    (net (code "66") (name "PWM13") (class "Default")
      (node (ref "R13") (pin "1") (pinfunction "1_1") (pintype "passive"))
      (node (ref "SERVO_DRIVER") (pin "20") (pinfunction "LED13_20") (pintype "bidirectional"))
    )
    (net (code "67") (name "PWM14") (class "Default")
      (node (ref "R16") (pin "1") (pinfunction "1_1") (pintype "passive"))
      (node (ref "SERVO_DRIVER") (pin "21") (pinfunction "LED14_21") (pintype "bidirectional"))
    )
    (net (code "68") (name "PWM15") (class "Default")
      (node (ref "R17") (pin "1") (pinfunction "1_1") (pintype "passive"))
      (node (ref "SERVO_DRIVER") (pin "22") (pinfunction "LED15_22") (pintype "bidirectional"))
    )
    (net (code "69") (name "RADIO_EN") (class "Default")
      (node (ref "RADIO") (pin "3") (pinfunction "EN_3") (pintype "bidirectional"))
      (node (ref "TEENSY4.1") (pin "32-OUT1B") (pinfunction "32-OUT1B_32-OUT1B") (pintype "bidirectional"))
    )
    (net (code "70") (name "RADIO_INT") (class "Default")
      (node (ref "RADIO") (pin "4") (pinfunction "G0_4") (pintype "bidirectional"))
      (node (ref "TEENSY4.1") (pin "30-CRX3") (pinfunction "30-CRX3_30-CRX3") (pintype "bidirectional"))
    )
    (net (code "71") (name "RADIO_RST") (class "Default")
      (node (ref "RADIO") (pin "9") (pinfunction "RST_9") (pintype "bidirectional"))
      (node (ref "TEENSY4.1") (pin "9-OUT1C") (pinfunction "9-OUT1C_9-OUT1C") (pintype "bidirectional"))
    )
    (net (code "72") (name "RX2") (class "Default")
      (node (ref "GPSMTK3339") (pin "TX") (pinfunction "TX_TX") (pintype "bidirectional"))
      (node (ref "TEENSY4.1") (pin "7-RX2/OUT1A") (pinfunction "7-RX2/OUT1A_7-RX2/OUT1A") (pintype "bidirectional"))
    )
    (net (code "73") (name "R_LED") (class "Default")
      (node (ref "RED") (pin "1") (pinfunction "1_1") (pintype "passive"))
      (node (ref "TEENSY4.1") (pin "41-A17/MISO1") (pinfunction "41-A17/MISO1_41-A17/MISO1") (pintype "bidirectional"))
    )
    (net (code "74") (name "SCK") (class "Default")
      (node (ref "U1") (pin "SCK") (pinfunction "SCK_SCK") (pintype "bidirectional"))
    )
    (net (code "75") (name "SCK0") (class "Default")
      (node (ref "RADIO") (pin "5") (pinfunction "SCK_5") (pintype "bidirectional"))
      (node (ref "TEENSY4.1") (pin "13-SCK/LED") (pinfunction "13-SCK/LED_13-SCK/LED") (pintype "bidirectional"))
    )
    (net (code "76") (name "SCL") (class "Default")
      (node (ref "IMU") (pin "SCL") (pinfunction "SCL_SCL") (pintype "bidirectional"))
      (node (ref "NAV") (pin "4") (pinfunction "4_4") (pintype "passive"))
      (node (ref "R32") (pin "1") (pinfunction "1_1") (pintype "passive"))
      (node (ref "SERVO_DRIVER") (pin "26") (pinfunction "SCL_26") (pintype "bidirectional"))
      (node (ref "TEENSY4.1") (pin "19-A5/SCL0") (pinfunction "19-A5/SCL0_19-A5/SCL0") (pintype "bidirectional"))
      (node (ref "TP3") (pin "TP") (pinfunction "TP_TP") (pintype "input"))
    )
    (net (code "77") (name "SDA") (class "Default")
      (node (ref "IMU") (pin "SDA") (pinfunction "SDA_SDA") (pintype "bidirectional"))
      (node (ref "NAV") (pin "3") (pinfunction "3_3") (pintype "passive"))
      (node (ref "R33") (pin "1") (pinfunction "1_1") (pintype "passive"))
      (node (ref "SERVO_DRIVER") (pin "27") (pinfunction "SDA_27") (pintype "bidirectional"))
      (node (ref "TEENSY4.1") (pin "18-A4/SDA0") (pinfunction "18-A4/SDA0_18-A4/SDA0") (pintype "bidirectional"))
      (node (ref "TP2") (pin "TP") (pinfunction "TP_TP") (pintype "input"))
    )
    (net (code "78") (name "SDI") (class "Default")
      (node (ref "U1") (pin "SDI") (pinfunction "SDI_SDI") (pintype "bidirectional"))
    )
    (net (code "79") (name "SDO") (class "Default")
      (node (ref "U1") (pin "SDO") (pinfunction "SDO_SDO") (pintype "bidirectional"))
    )
    (net (code "80") (name "SELECT_PIN") (class "Default")
      (node (ref "NAV") (pin "2") (pinfunction "2_2") (pintype "passive"))
      (node (ref "R23") (pin "2") (pinfunction "2_2") (pintype "passive"))
      (node (ref "TEENSY4.1") (pin "2-OUT2") (pinfunction "2-OUT2_2-OUT2") (pintype "bidirectional"))
    )
    (net (code "81") (name "TX2") (class "Default")
      (node (ref "GPSMTK3339") (pin "RX") (pinfunction "RX_RX") (pintype "bidirectional"))
      (node (ref "TEENSY4.1") (pin "8-TX2/IN1") (pinfunction "8-TX2/IN1_8-TX2/IN1") (pintype "bidirectional"))
    )
    (net (code "82") (name "VIN") (class "Default")
      (node (ref "U1") (pin "VIN") (pinfunction "VIN_VIN") (pintype "power_in"))
    )
    (net (code "83") (name "W_LED") (class "Default")
      (node (ref "TEENSY4.1") (pin "38-A14/CS/IN1") (pinfunction "38-A14/CS/IN1_38-A14/CS/IN1") (pintype "bidirectional"))
      (node (ref "WHITE") (pin "1") (pinfunction "1_1") (pintype "passive"))
    )
    (net (code "84") (name "Y_LED") (class "Default")
      (node (ref "TEENSY4.1") (pin "39-A15/CS/OUT1A") (pinfunction "39-A15/CS/OUT1A_39-A15/CS/OUT1A") (pintype "bidirectional"))
      (node (ref "YELLOW") (pin "1") (pinfunction "1_1") (pintype "passive"))
    )
    (net (code "85") (name "unconnected-(AUX-Pad2)") (class "Default")
      (node (ref "AUX") (pin "2") (pinfunction "2_2") (pintype "passive"))
    )
    (net (code "86") (name "unconnected-(C1-Pad2)") (class "Default")
      (node (ref "C1") (pin "2") (pinfunction "2_2") (pintype "passive"))
    )
    (net (code "87") (name "unconnected-(GPSMTK3339-Pad3.3V)") (class "Default")
      (node (ref "GPSMTK3339") (pin "3.3V") (pinfunction "3.3V_3.3V") (pintype "bidirectional"))
    )
    (net (code "88") (name "unconnected-(GPSMTK3339-PadVBAT)") (class "Default")
      (node (ref "GPSMTK3339") (pin "VBAT") (pinfunction "VBAT_VBAT") (pintype "bidirectional"))
    )
    (net (code "89") (name "unconnected-(IC3-COMP-Pad4)") (class "Default")
      (node (ref "IC3") (pin "4") (pinfunction "COMP_4") (pintype "bidirectional"))
    )
    (net (code "90") (name "unconnected-(IC3-EP-Pad9)") (class "Default")
      (node (ref "IC3") (pin "9") (pinfunction "EP_9") (pintype "bidirectional"))
    )
    (net (code "91") (name "unconnected-(IC3-SYNCH-Pad2)") (class "Default")
      (node (ref "IC3") (pin "2") (pinfunction "SYNCH_2") (pintype "bidirectional"))
    )
    (net (code "92") (name "unconnected-(RADIO-G1-Pad10)") (class "Default")
      (node (ref "RADIO") (pin "10") (pinfunction "G1_10") (pintype "bidirectional"))
    )
    (net (code "93") (name "unconnected-(RADIO-G2-Pad11)") (class "Default")
      (node (ref "RADIO") (pin "11") (pinfunction "G2_11") (pintype "bidirectional"))
    )
    (net (code "94") (name "unconnected-(RADIO-G3-Pad12)") (class "Default")
      (node (ref "RADIO") (pin "12") (pinfunction "G3_12") (pintype "bidirectional"))
    )
    (net (code "95") (name "unconnected-(RADIO-G4-Pad13)") (class "Default")
      (node (ref "RADIO") (pin "13") (pinfunction "G4_13") (pintype "bidirectional"))
    )
    (net (code "96") (name "unconnected-(RADIO-G5-Pad14)") (class "Default")
      (node (ref "RADIO") (pin "14") (pinfunction "G5_14") (pintype "bidirectional"))
    )
    (net (code "97") (name "unconnected-(TEENSY4.1-5V-Pad+5V)") (class "Default")
      (node (ref "TEENSY4.1") (pin "+5V") (pinfunction "5V_+5V") (pintype "bidirectional"))
    )
    (net (code "98") (name "unconnected-(TEENSY4.1-Pad0-RX1{slash}CS1{slash}CRX2)") (class "Default")
      (node (ref "TEENSY4.1") (pin "0-RX1/CS1/CRX2") (pinfunction "0-RX1/CS1/CRX2_0-RX1/CS1/CRX2") (pintype "bidirectional"))
    )
    (net (code "99") (name "unconnected-(TEENSY4.1-Pad1-TX1{slash}MISO1{slash}CTX2)") (class "Default")
      (node (ref "TEENSY4.1") (pin "1-TX1/MISO1/CTX2") (pinfunction "1-TX1/MISO1/CTX2_1-TX1/MISO1/CTX2") (pintype "bidirectional"))
    )
    (net (code "100") (name "unconnected-(TEENSY4.1-Pad16-A2{slash}RX4{slash}SCL1)") (class "Default")
      (node (ref "TEENSY4.1") (pin "16-A2/RX4/SCL1") (pinfunction "16-A2/RX4/SCL1_16-A2/RX4/SCL1") (pintype "bidirectional"))
    )
    (net (code "101") (name "unconnected-(TEENSY4.1-Pad17-A3{slash}TX4{slash}SDA1)") (class "Default")
      (node (ref "TEENSY4.1") (pin "17-A3/TX4/SDA1") (pinfunction "17-A3/TX4/SDA1_17-A3/TX4/SDA1") (pintype "bidirectional"))
    )
    (net (code "102") (name "unconnected-(TEENSY4.1-Pad20-A6{slash}TX5{slash}LRCLK1)") (class "Default")
      (node (ref "TEENSY4.1") (pin "20-A6/TX5/LRCLK1") (pinfunction "20-A6/TX5/LRCLK1_20-A6/TX5/LRCLK1") (pintype "bidirectional"))
    )
    (net (code "103") (name "unconnected-(TEENSY4.1-Pad21-A7{slash}RX5{slash}BCLK1)") (class "Default")
      (node (ref "TEENSY4.1") (pin "21-A7/RX5/BCLK1") (pinfunction "21-A7/RX5/BCLK1_21-A7/RX5/BCLK1") (pintype "bidirectional"))
    )
    (net (code "104") (name "unconnected-(TEENSY4.1-Pad23-A9{slash}CRX1{slash}MCLK1)") (class "Default")
      (node (ref "TEENSY4.1") (pin "23-A9/CRX1/MCLK1") (pinfunction "23-A9/CRX1/MCLK1_23-A9/CRX1/MCLK1") (pintype "bidirectional"))
    )
    (net (code "105") (name "unconnected-(TEENSY4.1-Pad28-RX7)") (class "Default")
      (node (ref "TEENSY4.1") (pin "28-RX7") (pinfunction "28-RX7_28-RX7") (pintype "bidirectional"))
    )
    (net (code "106") (name "unconnected-(TEENSY4.1-Pad29-TX7)") (class "Default")
      (node (ref "TEENSY4.1") (pin "29-TX7") (pinfunction "29-TX7_29-TX7") (pintype "bidirectional"))
    )
    (net (code "107") (name "unconnected-(TEENSY4.1-Pad31-CTX3)") (class "Default")
      (node (ref "TEENSY4.1") (pin "31-CTX3") (pinfunction "31-CTX3_31-CTX3") (pintype "bidirectional"))
    )
    (net (code "108") (name "unconnected-(TEENSY4.1-PadD+)") (class "Default")
      (node (ref "TEENSY4.1") (pin "D+") (pinfunction "D+_D+") (pintype "bidirectional"))
    )
    (net (code "109") (name "unconnected-(TEENSY4.1-PadD-)") (class "Default")
      (node (ref "TEENSY4.1") (pin "D-") (pinfunction "D-_D-") (pintype "bidirectional"))
    )
    (net (code "110") (name "unconnected-(TEENSY4.1-PadDM)") (class "Default")
      (node (ref "TEENSY4.1") (pin "DM") (pinfunction "DM_DM") (pintype "bidirectional"))
    )
    (net (code "111") (name "unconnected-(TEENSY4.1-PadDP)") (class "Default")
      (node (ref "TEENSY4.1") (pin "DP") (pinfunction "DP_DP") (pintype "bidirectional"))
    )
    (net (code "112") (name "unconnected-(TEENSY4.1-PadG)") (class "Default")
      (node (ref "TEENSY4.1") (pin "G") (pinfunction "G_G") (pintype "bidirectional"))
    )
    (net (code "113") (name "unconnected-(TEENSY4.1-PadLED)") (class "Default")
      (node (ref "TEENSY4.1") (pin "LED") (pinfunction "LED_LED") (pintype "bidirectional"))
    )
    (net (code "114") (name "unconnected-(TEENSY4.1-PadON{slash}OFF)") (class "Default")
      (node (ref "TEENSY4.1") (pin "ON/OFF") (pinfunction "ON/OFF_ON/OFF") (pintype "bidirectional"))
    )
    (net (code "115") (name "unconnected-(TEENSY4.1-PadPROGRAM)") (class "Default")
      (node (ref "TEENSY4.1") (pin "PROGRAM") (pinfunction "PROGRAM_PROGRAM") (pintype "bidirectional"))
    )
    (net (code "116") (name "unconnected-(TEENSY4.1-PadR+)") (class "Default")
      (node (ref "TEENSY4.1") (pin "R+") (pinfunction "R+_R+") (pintype "bidirectional"))
    )
    (net (code "117") (name "unconnected-(TEENSY4.1-PadR-)") (class "Default")
      (node (ref "TEENSY4.1") (pin "R-") (pinfunction "R-_R-") (pintype "bidirectional"))
    )
    (net (code "118") (name "unconnected-(TEENSY4.1-PadT+)") (class "Default")
      (node (ref "TEENSY4.1") (pin "T+") (pinfunction "T+_T+") (pintype "bidirectional"))
    )
    (net (code "119") (name "unconnected-(TEENSY4.1-PadT-)") (class "Default")
      (node (ref "TEENSY4.1") (pin "T-") (pinfunction "T-_T-") (pintype "bidirectional"))
    )
    (net (code "120") (name "unconnected-(TEENSY4.1-PadVBAT)") (class "Default")
      (node (ref "TEENSY4.1") (pin "VBAT") (pinfunction "VBAT_VBAT") (pintype "bidirectional"))
    )
    (net (code "121") (name "unconnected-(TEENSY4.1-PadVUSB)") (class "Default")
      (node (ref "TEENSY4.1") (pin "VUSB") (pinfunction "VUSB_VUSB") (pintype "bidirectional"))
    )
  )
)
